# Sheet1.net
KiCad netlist of a schematic drawn in Altium Designer
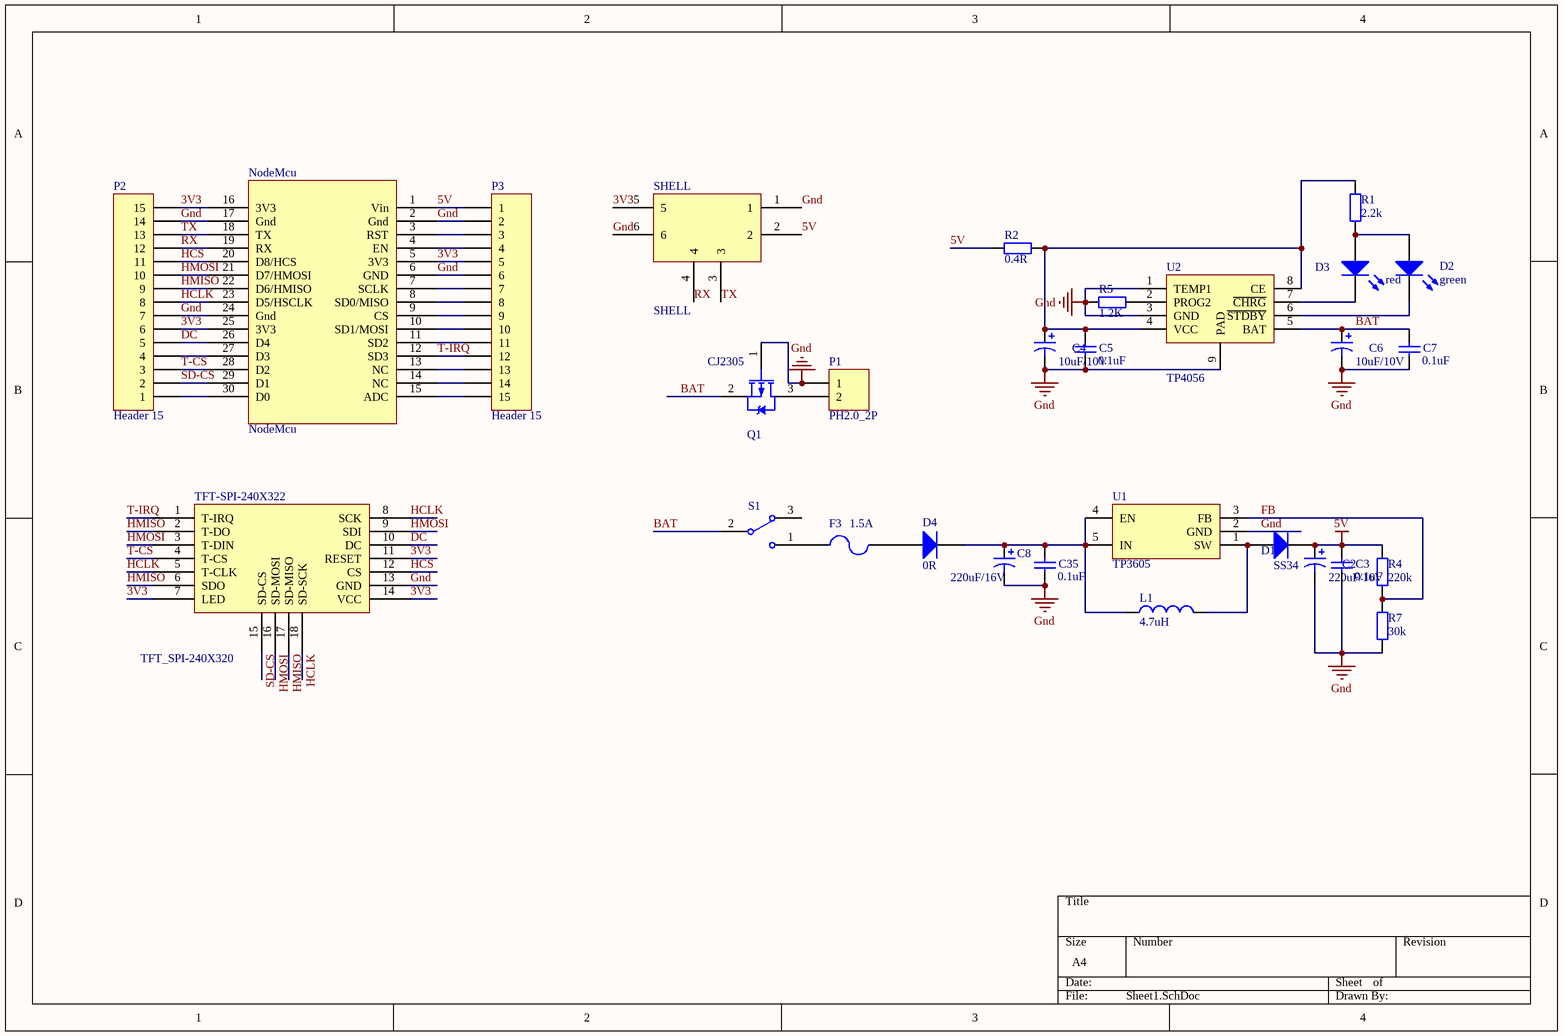
[diagram p0: Sheet1.SchDoc]

(export (version "E")
  (design (tool "Eeschema 10.0.6"))
  (components
    (comp (ref "C2")
      (value "220uF/16V")
      (footprint "SMT-EC-D6.3")
      (description "贴片电解电容 6.3X7.7")
      (fields (field (name "PUBLISHER") "Altium Limited"))
      (libsource (lib "Miscellaneous Devices") (part "Cap Pol1"))
    )
    (comp (ref "C3")
      (value "0.1uF")
      (footprint "C0603")
      (description "Capacitor 0603 10% 50V")
      (fields (field (name "PUBLISHER") "Altium Limited"))
      (libsource (lib "Miscellaneous Devices") (part "Cap"))
    )
    (comp (ref "C4")
      (value "10uF/10V")
      (footprint "C0805")
      (description "Capacitor 0805 10% 10V")
      (fields (field (name "PUBLISHER") "Altium Limited"))
      (libsource (lib "Miscellaneous Devices") (part "Cap Pol1"))
    )
    (comp (ref "C5")
      (value "0.1uF")
      (footprint "C0603")
      (description "Capacitor 0603 10% 50V")
      (fields (field (name "PUBLISHER") "Altium Limited"))
      (libsource (lib "Miscellaneous Devices") (part "Cap"))
    )
    (comp (ref "C6")
      (value "10uF/10V")
      (footprint "C0805")
      (description "Capacitor 0805 10% 10V")
      (fields (field (name "PUBLISHER") "Altium Limited"))
      (libsource (lib "Miscellaneous Devices") (part "Cap Pol1"))
    )
    (comp (ref "C7")
      (value "0.1uF")
      (footprint "C0603")
      (description "Capacitor 0603 10% 50V")
      (fields (field (name "PUBLISHER") "Altium Limited"))
      (libsource (lib "Miscellaneous Devices") (part "Cap"))
    )
    (comp (ref "C8")
      (value "220uF/16V")
      (footprint "SMT-EC-D6.3")
      (description "贴片电解电容 6.3X7.7")
      (fields (field (name "PUBLISHER") "Altium Limited"))
      (libsource (lib "Miscellaneous Devices") (part "Cap Pol1"))
    )
    (comp (ref "C35")
      (value "0.1uF")
      (footprint "C0603")
      (description "Capacitor 0603 10% 50V")
      (fields (field (name "PUBLISHER") "Altium Limited"))
      (libsource (lib "Miscellaneous Devices") (part "Cap"))
    )
    (comp (ref "D1")
      (value "SS34")
      (footprint "DO-214")
      (description "Diode DO214-AC")
      (fields (field (name "PUBLISHER") "Altium Limited"))
      (libsource (lib "Miscellaneous Devices") (part "Diode"))
    )
    (comp (ref "D2")
      (value "green")
      (footprint "D0603")
      (description "LED, Red 0603 (1608)")
      (fields (field (name "PUBLISHER") "Altium Limited"))
      (libsource (lib "Miscellaneous Devices") (part "LED3"))
    )
    (comp (ref "D3")
      (value "red")
      (footprint "D0603")
      (description "LED, Red 0603 (1608)")
      (fields (field (name "PUBLISHER") "Altium Limited"))
      (libsource (lib "Miscellaneous Devices") (part "LED3"))
    )
    (comp (ref "D4")
      (value "0R")
      (footprint "DO-214")
      (description "0R 1% 1206")
      (fields (field (name "PUBLISHER") "Altium Limited"))
      (libsource (lib "Miscellaneous Devices") (part "Diode"))
    )
    (comp (ref "F3")
      (value "1.5A")
      (footprint "RESC4532AN")
      (description "自恢复保险丝 25V 1812")
      (fields (field (name "PUBLISHER") "Altium Limited"))
      (libsource (lib "Miscellaneous Devices") (part "Fuse 2"))
    )
    (comp (ref "L1")
      (value "4.7uH")
      (footprint "L4532")
      (description "GDCD4532-4R7MT")
      (fields (field (name "PUBLISHER") "Altium Limited"))
      (libsource (lib "Miscellaneous Devices") (part "Inductor"))
    )
    (comp (ref "NodeMcu")
      (value "NodeMcu")
      (footprint "NodeMcu")
      (libsource (lib "NodeMcu") (part "NodeMcu"))
    )
    (comp (ref "P1")
      (value "PH2.0_2P")
      (footprint "CON_PH2.0_2P")
      (fields (field (name "PUBLISHER") "Altium Limited"))
      (libsource (lib "Miscellaneous Connectors") (part "Header 2"))
    )
    (comp (ref "P2")
      (value "Header 15")
      (footprint "HDR1X15")
      (description "Header, 15-Pin")
      (fields (field (name "PUBLISHER") "Altium Limited"))
      (libsource (lib "") (part "Header 15_1"))
    )
    (comp (ref "P3")
      (value "Header 15")
      (footprint "HDR1X15")
      (description "Header, 15-Pin")
      (fields (field (name "PUBLISHER") "Altium Limited"))
      (libsource (lib "Miscellaneous Connectors") (part "Header 15"))
    )
    (comp (ref "Q1")
      (value "CJ2305")
      (footprint "SOT-23-3")
      (description "PMOS CJ2305 SOT-23")
      (libsource (lib "Mylib") (part "PMOS"))
    )
    (comp (ref "R1")
      (value "2.2k")
      (footprint "R0603")
      (description "Resistor,  1% 0603 (1608)")
      (fields (field (name "PUBLISHER") "Altium Limited"))
      (libsource (lib "Miscellaneous Devices") (part "Res2"))
    )
    (comp (ref "R2")
      (value "0.4R")
      (footprint "R0805")
      (description "Resistor,  1% 0805")
      (fields (field (name "PUBLISHER") "Altium Limited"))
      (libsource (lib "") (part "Res2_2"))
    )
    (comp (ref "R4")
      (value "220k")
      (footprint "R0603")
      (description "Resistor,  1% 0603 (1608)")
      (fields (field (name "PUBLISHER") "Altium Limited"))
      (libsource (lib "Miscellaneous Devices") (part "Res2"))
    )
    (comp (ref "R5")
      (value "1.2K")
      (footprint "R0603")
      (description "Resistor,  1% 0603 (1608)")
      (fields (field (name "PUBLISHER") "Altium Limited"))
      (libsource (lib "") (part "Res2_1"))
    )
    (comp (ref "R7")
      (value "30k")
      (footprint "R0603")
      (description "Resistor,  1% 0603 (1608)")
      (fields (field (name "PUBLISHER") "Altium Limited"))
      (libsource (lib "Miscellaneous Devices") (part "Res2"))
    )
    (comp (ref "S1")
      (value "SS-12D06")
      (footprint "SW-SS-12D06")
      (description "二档大拨动开关弯角拨动开关SS-12D06")
      (fields (field (name "PUBLISHER") "Altium Limited"))
      (libsource (lib "Miscellaneous Devices") (part "SW-SPDT"))
    )
    (comp (ref "SHELL") (value "SHELL") (footprint "SHELL") (libsource (lib "NodeMcu") (part "SHELL")))
    (comp (ref "TFT-SPI-240X322")
      (value "TFT_SPI-240X320")
      (footprint "TFT-SPI-240X320")
      (libsource (lib "NodeMcu") (part "TFT_SPI-240X320"))
    )
    (comp (ref "U1")
      (value "TP3605")
      (footprint "SOT-23-6")
      (description "电源 升压 IC")
      (libsource (lib "makeblock") (part "MP1540DJ"))
    )
    (comp (ref "U2")
      (value "TP4056")
      (footprint "SOIC127P600-8DN")
      (description "锂电池充电IC")
      (libsource (lib "makeblock") (part "TP4056"))
    )
  )
  (nets
    (net (code "1") (name "/3V3") (class "Default")
      (node (ref "NodeMcu") (pin "16") (pinfunction "3V3_16") (pintype "passive"))
      (node (ref "NodeMcu") (pin "25") (pinfunction "3V3_25") (pintype "passive"))
      (node (ref "NodeMcu") (pin "5") (pinfunction "3V3_5") (pintype "passive"))
      (node (ref "P2") (pin "15") (pinfunction "15_15") (pintype "passive"))
      (node (ref "P2") (pin "6") (pinfunction "6_6") (pintype "passive"))
      (node (ref "P3") (pin "5") (pinfunction "5_5") (pintype "passive"))
      (node (ref "SHELL") (pin "5") (pinfunction "5_5") (pintype "passive"))
      (node (ref "TFT-SPI-240X322") (pin "11") (pinfunction "RESET_11") (pintype "passive"))
      (node (ref "TFT-SPI-240X322") (pin "14") (pinfunction "VCC_14") (pintype "passive"))
      (node (ref "TFT-SPI-240X322") (pin "7") (pinfunction "LED_7") (pintype "passive"))
    )
    (net (code "2") (name "/BAT") (class "Default")
      (node (ref "C6") (pin "1") (pinfunction "1_1") (pintype "passive"))
      (node (ref "C7") (pin "1") (pinfunction "1_1") (pintype "passive"))
      (node (ref "Q1") (pin "2") (pinfunction "S_2") (pintype "passive"))
      (node (ref "S1") (pin "2") (pinfunction "2_2") (pintype "passive"))
      (node (ref "U2") (pin "5") (pinfunction "BAT_5") (pintype "passive"))
    )
    (net (code "3") (name "/DC") (class "Default")
      (node (ref "NodeMcu") (pin "26") (pinfunction "D4_26") (pintype "passive"))
      (node (ref "P2") (pin "5") (pinfunction "5_5") (pintype "passive"))
      (node (ref "TFT-SPI-240X322") (pin "10") (pinfunction "DC_10") (pintype "passive"))
    )
    (net (code "4") (name "/FB") (class "Default")
      (node (ref "R4") (pin "1") (pinfunction "1_1") (pintype "passive"))
      (node (ref "R7") (pin "2") (pinfunction "2_2") (pintype "passive"))
      (node (ref "U1") (pin "3") (pinfunction "FB_3") (pintype "passive"))
    )
    (net (code "5") (name "/HCLK") (class "Default")
      (node (ref "NodeMcu") (pin "23") (pinfunction "D5/HSCLK_23") (pintype "passive"))
      (node (ref "P2") (pin "8") (pinfunction "8_8") (pintype "passive"))
      (node (ref "TFT-SPI-240X322") (pin "18") (pinfunction "SD-SCK_18") (pintype "passive"))
      (node (ref "TFT-SPI-240X322") (pin "5") (pinfunction "T-CLK_5") (pintype "passive"))
      (node (ref "TFT-SPI-240X322") (pin "8") (pinfunction "SCK_8") (pintype "passive"))
    )
    (net (code "6") (name "/HCS") (class "Default")
      (node (ref "NodeMcu") (pin "20") (pinfunction "D8/HCS_20") (pintype "passive"))
      (node (ref "P2") (pin "11") (pinfunction "11_11") (pintype "passive"))
      (node (ref "TFT-SPI-240X322") (pin "12") (pinfunction "CS_12") (pintype "passive"))
    )
    (net (code "7") (name "/HMISO") (class "Default")
      (node (ref "NodeMcu") (pin "22") (pinfunction "D6/HMISO_22") (pintype "passive"))
      (node (ref "P2") (pin "9") (pinfunction "9_9") (pintype "passive"))
      (node (ref "TFT-SPI-240X322") (pin "17") (pinfunction "SD-MISO_17") (pintype "passive"))
      (node (ref "TFT-SPI-240X322") (pin "2") (pinfunction "T-DO_2") (pintype "passive"))
      (node (ref "TFT-SPI-240X322") (pin "6") (pinfunction "SDO_6") (pintype "passive"))
    )
    (net (code "8") (name "/HMOSI") (class "Default")
      (node (ref "NodeMcu") (pin "21") (pinfunction "D7/HMOSI_21") (pintype "passive"))
      (node (ref "P2") (pin "10") (pinfunction "10_10") (pintype "passive"))
      (node (ref "TFT-SPI-240X322") (pin "16") (pinfunction "SD-MOSI_16") (pintype "passive"))
      (node (ref "TFT-SPI-240X322") (pin "3") (pinfunction "T-DIN_3") (pintype "passive"))
      (node (ref "TFT-SPI-240X322") (pin "9") (pinfunction "SDI_9") (pintype "passive"))
    )
    (net (code "9") (name "/RX") (class "Default")
      (node (ref "NodeMcu") (pin "19") (pinfunction "RX_19") (pintype "passive"))
      (node (ref "P2") (pin "12") (pinfunction "12_12") (pintype "passive"))
      (node (ref "SHELL") (pin "4") (pinfunction "4_4") (pintype "passive"))
    )
    (net (code "10") (name "/SD-CS") (class "Default")
      (node (ref "NodeMcu") (pin "29") (pinfunction "D1_29") (pintype "passive"))
      (node (ref "P2") (pin "2") (pinfunction "2_2") (pintype "passive"))
      (node (ref "TFT-SPI-240X322") (pin "15") (pinfunction "SD-CS_15") (pintype "passive"))
    )
    (net (code "11") (name "/T-CS") (class "Default")
      (node (ref "NodeMcu") (pin "28") (pinfunction "D2_28") (pintype "passive"))
      (node (ref "P2") (pin "3") (pinfunction "3_3") (pintype "passive"))
      (node (ref "TFT-SPI-240X322") (pin "4") (pinfunction "T-CS_4") (pintype "passive"))
    )
    (net (code "12") (name "/T-IRQ") (class "Default")
      (node (ref "NodeMcu") (pin "12") (pinfunction "SD3_12") (pintype "passive"))
      (node (ref "P3") (pin "12") (pinfunction "12_12") (pintype "passive"))
      (node (ref "TFT-SPI-240X322") (pin "1") (pinfunction "T-IRQ_1") (pintype "passive"))
    )
    (net (code "13") (name "/TX") (class "Default")
      (node (ref "NodeMcu") (pin "18") (pinfunction "TX_18") (pintype "passive"))
      (node (ref "P2") (pin "13") (pinfunction "13_13") (pintype "passive"))
      (node (ref "SHELL") (pin "3") (pinfunction "3_3") (pintype "passive"))
    )
    (net (code "14") (name "5V") (class "Default")
      (node (ref "C2") (pin "1") (pinfunction "1_1") (pintype "passive"))
      (node (ref "C3") (pin "1") (pinfunction "1_1") (pintype "passive"))
      (node (ref "D1") (pin "2") (pinfunction "K_2") (pintype "passive"))
      (node (ref "NodeMcu") (pin "1") (pinfunction "Vin_1") (pintype "passive"))
      (node (ref "P3") (pin "1") (pinfunction "1_1") (pintype "passive"))
      (node (ref "R2") (pin "2") (pinfunction "2_2") (pintype "passive"))
      (node (ref "R4") (pin "2") (pinfunction "2_2") (pintype "passive"))
      (node (ref "SHELL") (pin "2") (pinfunction "2_2") (pintype "passive"))
    )
    (net (code "15") (name "Gnd") (class "Default")
      (node (ref "C2") (pin "2") (pinfunction "2_2") (pintype "passive"))
      (node (ref "C3") (pin "2") (pinfunction "2_2") (pintype "passive"))
      (node (ref "C35") (pin "2") (pinfunction "2_2") (pintype "passive"))
      (node (ref "C4") (pin "2") (pinfunction "2_2") (pintype "passive"))
      (node (ref "C5") (pin "2") (pinfunction "2_2") (pintype "passive"))
      (node (ref "C6") (pin "2") (pinfunction "2_2") (pintype "passive"))
      (node (ref "C7") (pin "2") (pinfunction "2_2") (pintype "passive"))
      (node (ref "C8") (pin "2") (pinfunction "2_2") (pintype "passive"))
      (node (ref "NodeMcu") (pin "17") (pinfunction "Gnd_17") (pintype "passive"))
      (node (ref "NodeMcu") (pin "2") (pinfunction "Gnd_2") (pintype "passive"))
      (node (ref "NodeMcu") (pin "24") (pinfunction "Gnd_24") (pintype "passive"))
      (node (ref "NodeMcu") (pin "6") (pinfunction "GND_6") (pintype "passive"))
      (node (ref "P1") (pin "1") (pinfunction "1_1") (pintype "passive"))
      (node (ref "P2") (pin "14") (pinfunction "14_14") (pintype "passive"))
      (node (ref "P2") (pin "7") (pinfunction "7_7") (pintype "passive"))
      (node (ref "P3") (pin "2") (pinfunction "2_2") (pintype "passive"))
      (node (ref "P3") (pin "6") (pinfunction "6_6") (pintype "passive"))
      (node (ref "Q1") (pin "1") (pinfunction "G_1") (pintype "passive"))
      (node (ref "R5") (pin "1") (pinfunction "1_1") (pintype "passive"))
      (node (ref "R7") (pin "1") (pinfunction "1_1") (pintype "passive"))
      (node (ref "SHELL") (pin "1") (pinfunction "1_1") (pintype "passive"))
      (node (ref "SHELL") (pin "6") (pinfunction "6_6") (pintype "passive"))
      (node (ref "TFT-SPI-240X322") (pin "13") (pinfunction "GND_13") (pintype "passive"))
      (node (ref "U1") (pin "2") (pinfunction "GND_2") (pintype "passive"))
      (node (ref "U2") (pin "1") (pinfunction "TEMP1_1") (pintype "passive"))
      (node (ref "U2") (pin "3") (pinfunction "GND_3") (pintype "passive"))
      (node (ref "U2") (pin "9") (pinfunction "PAD_9") (pintype "passive"))
    )
    (net (code "16") (name "Net-(D1-A)") (class "Default")
      (node (ref "D1") (pin "1") (pinfunction "A_1") (pintype "passive"))
      (node (ref "L1") (pin "2") (pinfunction "2_2") (pintype "passive"))
      (node (ref "U1") (pin "1") (pinfunction "SW_1") (pintype "passive"))
    )
    (net (code "17") (name "Net-(D2-A)") (class "Default")
      (node (ref "D2") (pin "1") (pinfunction "A_1") (pintype "passive"))
      (node (ref "D3") (pin "1") (pinfunction "A_1") (pintype "passive"))
      (node (ref "R1") (pin "1") (pinfunction "1_1") (pintype "passive"))
    )
    (net (code "18") (name "Net-(D2-K)") (class "Default")
      (node (ref "D2") (pin "2") (pinfunction "K_2") (pintype "passive"))
      (node (ref "U2") (pin "6") (pinfunction "~{STDBY}_6") (pintype "passive"))
    )
    (net (code "19") (name "Net-(D3-K)") (class "Default")
      (node (ref "D3") (pin "2") (pinfunction "K_2") (pintype "passive"))
      (node (ref "U2") (pin "7") (pinfunction "~{CHRG}_7") (pintype "passive"))
    )
    (net (code "20") (name "Net-(D4-A)") (class "Default")
      (node (ref "D4") (pin "1") (pinfunction "A_1") (pintype "passive"))
      (node (ref "F3") (pin "2") (pinfunction "2_2") (pintype "passive"))
    )
    (net (code "21") (name "Net-(D4-K)") (class "Default")
      (node (ref "C35") (pin "1") (pinfunction "1_1") (pintype "passive"))
      (node (ref "C8") (pin "1") (pinfunction "1_1") (pintype "passive"))
      (node (ref "D4") (pin "2") (pinfunction "K_2") (pintype "passive"))
      (node (ref "L1") (pin "1") (pinfunction "1_1") (pintype "passive"))
      (node (ref "U1") (pin "4") (pinfunction "EN_4") (pintype "passive"))
      (node (ref "U1") (pin "5") (pinfunction "IN_5") (pintype "passive"))
    )
    (net (code "22") (name "Net-(F3-Pad1)") (class "Default")
      (node (ref "F3") (pin "1") (pinfunction "1_1") (pintype "passive"))
      (node (ref "S1") (pin "1") (pinfunction "1_1") (pintype "passive"))
    )
    (net (code "23") (name "Net-(NodeMcu-ADC)") (class "Default")
      (node (ref "NodeMcu") (pin "15") (pinfunction "ADC_15") (pintype "passive"))
      (node (ref "P3") (pin "15") (pinfunction "15_15") (pintype "passive"))
    )
    (net (code "24") (name "Net-(NodeMcu-CS)") (class "Default")
      (node (ref "NodeMcu") (pin "9") (pinfunction "CS_9") (pintype "passive"))
      (node (ref "P3") (pin "9") (pinfunction "9_9") (pintype "passive"))
    )
    (net (code "25") (name "Net-(NodeMcu-D0)") (class "Default")
      (node (ref "NodeMcu") (pin "30") (pinfunction "D0_30") (pintype "passive"))
      (node (ref "P2") (pin "1") (pinfunction "1_1") (pintype "passive"))
    )
    (net (code "26") (name "Net-(NodeMcu-D3)") (class "Default")
      (node (ref "NodeMcu") (pin "27") (pinfunction "D3_27") (pintype "passive"))
      (node (ref "P2") (pin "4") (pinfunction "4_4") (pintype "passive"))
    )
    (net (code "27") (name "Net-(NodeMcu-EN)") (class "Default")
      (node (ref "NodeMcu") (pin "4") (pinfunction "EN_4") (pintype "passive"))
      (node (ref "P3") (pin "4") (pinfunction "4_4") (pintype "passive"))
    )
    (net (code "28") (name "Net-(NodeMcu-NC-Pad13)") (class "Default")
      (node (ref "NodeMcu") (pin "13") (pinfunction "NC_13") (pintype "passive"))
      (node (ref "P3") (pin "13") (pinfunction "13_13") (pintype "passive"))
    )
    (net (code "29") (name "Net-(NodeMcu-NC-Pad14)") (class "Default")
      (node (ref "NodeMcu") (pin "14") (pinfunction "NC_14") (pintype "passive"))
      (node (ref "P3") (pin "14") (pinfunction "14_14") (pintype "passive"))
    )
    (net (code "30") (name "Net-(NodeMcu-RST)") (class "Default")
      (node (ref "NodeMcu") (pin "3") (pinfunction "RST_3") (pintype "passive"))
      (node (ref "P3") (pin "3") (pinfunction "3_3") (pintype "passive"))
    )
    (net (code "31") (name "Net-(NodeMcu-SCLK)") (class "Default")
      (node (ref "NodeMcu") (pin "7") (pinfunction "SCLK_7") (pintype "passive"))
      (node (ref "P3") (pin "7") (pinfunction "7_7") (pintype "passive"))
    )
    (net (code "32") (name "Net-(NodeMcu-SD0{slash}MISO)") (class "Default")
      (node (ref "NodeMcu") (pin "8") (pinfunction "SD0/MISO_8") (pintype "passive"))
      (node (ref "P3") (pin "8") (pinfunction "8_8") (pintype "passive"))
    )
    (net (code "33") (name "Net-(NodeMcu-SD1{slash}MOSI)") (class "Default")
      (node (ref "NodeMcu") (pin "10") (pinfunction "SD1/MOSI_10") (pintype "passive"))
      (node (ref "P3") (pin "10") (pinfunction "10_10") (pintype "passive"))
    )
    (net (code "34") (name "Net-(NodeMcu-SD2)") (class "Default")
      (node (ref "NodeMcu") (pin "11") (pinfunction "SD2_11") (pintype "passive"))
      (node (ref "P3") (pin "11") (pinfunction "11_11") (pintype "passive"))
    )
    (net (code "35") (name "Net-(Q1-D)") (class "Default")
      (node (ref "P1") (pin "2") (pinfunction "2_2") (pintype "passive"))
      (node (ref "Q1") (pin "3") (pinfunction "D_3") (pintype "passive"))
    )
    (net (code "36") (name "Net-(U2-CE)") (class "Default")
      (node (ref "C4") (pin "1") (pinfunction "1_1") (pintype "passive"))
      (node (ref "C5") (pin "1") (pinfunction "1_1") (pintype "passive"))
      (node (ref "R1") (pin "2") (pinfunction "2_2") (pintype "passive"))
      (node (ref "R2") (pin "1") (pinfunction "1_1") (pintype "passive"))
      (node (ref "U2") (pin "4") (pinfunction "VCC_4") (pintype "passive"))
      (node (ref "U2") (pin "8") (pinfunction "CE_8") (pintype "passive"))
    )
    (net (code "37") (name "Net-(U2-PROG2)") (class "Default")
      (node (ref "R5") (pin "2") (pinfunction "2_2") (pintype "passive"))
      (node (ref "U2") (pin "2") (pinfunction "PROG2_2") (pintype "passive"))
    )
    (net (code "38") (name "unconnected-(S1-Pad3)") (class "Default")
      (node (ref "S1") (pin "3") (pinfunction "3_3") (pintype "passive"))
    )
  )
)
